# unijoysticle.net
KiCad netlist of a schematic drawn in EAGLE
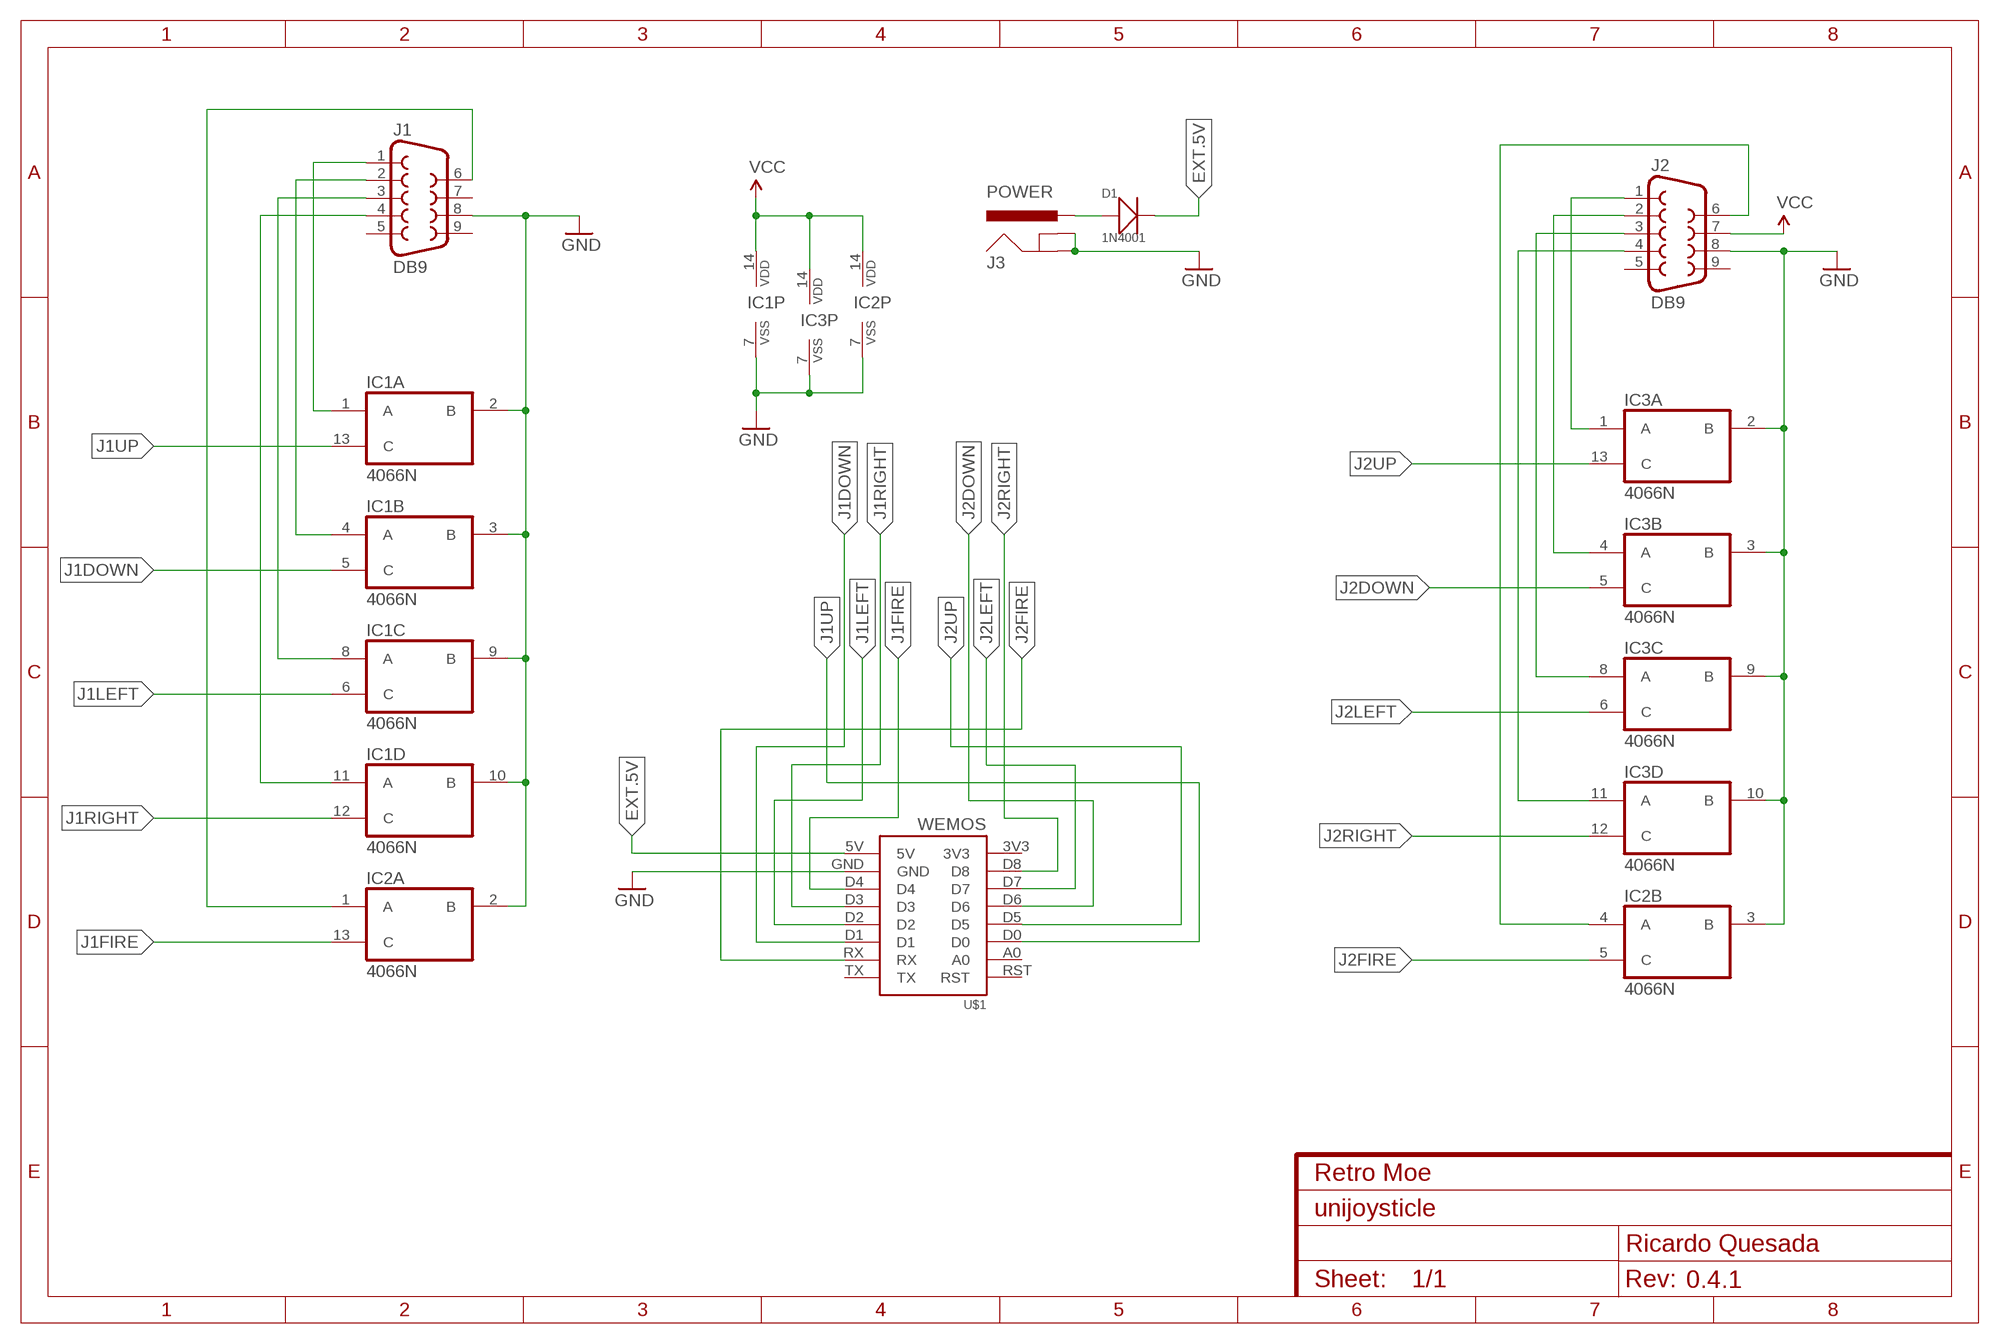
[diagram p0: schematic, sheet 1]

(export (version "E")
  (design (tool "Eeschema 10.0.6"))
  (components
    (comp (ref "D1")
      (value "1N4001")
      (footprint "eagle-import:DO-41")
      (libsource (lib "eagle-import") (part "DIP-DIODE-50V-1A-1N4001(DO-41)"))
    )
    (comp (ref "IC1")
      (value "4066N")
      (footprint "eagle-import:DIL14")
      (fields
        (field (name "MF") "TEXAS INSTRUMENTS")
        (field (name "MPN") "SN74HC4066N")
        (field (name "OC_NEWARK") "76C3574")
      )
      (libsource (lib "eagle-import") (part "4066N"))
    )
    (comp (ref "IC2")
      (value "4066N")
      (footprint "eagle-import:DIL14")
      (fields
        (field (name "MF") "TEXAS INSTRUMENTS")
        (field (name "MPN") "SN74HC4066N")
        (field (name "OC_NEWARK") "76C3574")
      )
      (libsource (lib "eagle-import") (part "4066N"))
    )
    (comp (ref "IC3")
      (value "4066N")
      (footprint "eagle-import:DIL14")
      (fields
        (field (name "MF") "TEXAS INSTRUMENTS")
        (field (name "MPN") "SN74HC4066N")
        (field (name "OC_NEWARK") "76C3574")
      )
      (libsource (lib "eagle-import") (part "4066N"))
    )
    (comp (ref "J1")
      (value "DB9")
      (footprint "eagle-import:DB9")
      (fields (field (name "MPN") "618009231121"))
      (libsource (lib "eagle-import") (part "DB9FEMALE"))
    )
    (comp (ref "J2")
      (value "DB9")
      (footprint "eagle-import:DB9")
      (fields (field (name "MPN") "618009231121"))
      (libsource (lib "eagle-import") (part "DB9FEMALE"))
    )
    (comp (ref "J3")
      (value "POWER")
      (footprint "eagle-import:POWER_JACK_SLOT")
      (libsource (lib "eagle-import") (part "POWER_JACKSLT"))
    )
    (comp (ref "U$1")
      (value "WEMOS")
      (footprint "eagle-import:WEMOS")
      (libsource (lib "eagle-import") (part "WEMOS"))
    )
  )
  (nets
    (net (code "1") (name "EXT.5V") (class "Default")
      (node (ref "D1") (pin "2") (pinfunction "-_2") (pintype "passive"))
      (node (ref "U$1") (pin "5V") (pinfunction "5V_5V") (pintype "bidirectional"))
    )
    (net (code "2") (name "GND") (class "Default")
      (node (ref "IC1") (pin "10") (pinfunction "B_10") (pintype "tri_state"))
      (node (ref "IC1") (pin "2") (pinfunction "B_2") (pintype "tri_state"))
      (node (ref "IC1") (pin "3") (pinfunction "B_3") (pintype "tri_state"))
      (node (ref "IC1") (pin "7") (pinfunction "VSS_7") (pintype "power_in"))
      (node (ref "IC1") (pin "9") (pinfunction "B_9") (pintype "tri_state"))
      (node (ref "IC2") (pin "2") (pinfunction "B_2") (pintype "tri_state"))
      (node (ref "IC2") (pin "3") (pinfunction "B_3") (pintype "tri_state"))
      (node (ref "IC2") (pin "7") (pinfunction "VSS_7") (pintype "power_in"))
      (node (ref "IC3") (pin "10") (pinfunction "B_10") (pintype "tri_state"))
      (node (ref "IC3") (pin "2") (pinfunction "B_2") (pintype "tri_state"))
      (node (ref "IC3") (pin "3") (pinfunction "B_3") (pintype "tri_state"))
      (node (ref "IC3") (pin "7") (pinfunction "VSS_7") (pintype "power_in"))
      (node (ref "IC3") (pin "9") (pinfunction "B_9") (pintype "tri_state"))
      (node (ref "J1") (pin "8") (pinfunction "8_8") (pintype "passive"))
      (node (ref "J2") (pin "8") (pinfunction "8_8") (pintype "passive"))
      (node (ref "J3") (pin "GND@1") (pinfunction "GNDBREAK_GND@1") (pintype "bidirectional"))
      (node (ref "J3") (pin "GND@2") (pinfunction "GND_GND@2") (pintype "bidirectional"))
      (node (ref "U$1") (pin "GND") (pinfunction "GND_GND") (pintype "bidirectional"))
    )
    (net (code "3") (name "J1DOWN") (class "Default")
      (node (ref "IC1") (pin "5") (pinfunction "C_5") (pintype "input"))
      (node (ref "U$1") (pin "D1") (pinfunction "D1_D1") (pintype "bidirectional"))
    )
    (net (code "4") (name "J1FIRE") (class "Default")
      (node (ref "IC2") (pin "13") (pinfunction "C_13") (pintype "input"))
      (node (ref "U$1") (pin "D4") (pinfunction "D4_D4") (pintype "bidirectional"))
    )
    (net (code "5") (name "J1LEFT") (class "Default")
      (node (ref "IC1") (pin "6") (pinfunction "C_6") (pintype "input"))
      (node (ref "U$1") (pin "D2") (pinfunction "D2_D2") (pintype "bidirectional"))
    )
    (net (code "6") (name "J1RIGHT") (class "Default")
      (node (ref "IC1") (pin "12") (pinfunction "C_12") (pintype "input"))
      (node (ref "U$1") (pin "D3") (pinfunction "D3_D3") (pintype "bidirectional"))
    )
    (net (code "7") (name "J1UP") (class "Default")
      (node (ref "IC1") (pin "13") (pinfunction "C_13") (pintype "input"))
      (node (ref "U$1") (pin "D0") (pinfunction "D0_D0") (pintype "bidirectional"))
    )
    (net (code "8") (name "J2DOWN") (class "Default")
      (node (ref "IC3") (pin "5") (pinfunction "C_5") (pintype "input"))
      (node (ref "U$1") (pin "D6") (pinfunction "D6_D6") (pintype "bidirectional"))
    )
    (net (code "9") (name "J2FIRE") (class "Default")
      (node (ref "IC2") (pin "5") (pinfunction "C_5") (pintype "input"))
      (node (ref "U$1") (pin "RX") (pinfunction "RX_RX") (pintype "bidirectional"))
    )
    (net (code "10") (name "J2LEFT") (class "Default")
      (node (ref "IC3") (pin "6") (pinfunction "C_6") (pintype "input"))
      (node (ref "U$1") (pin "D7") (pinfunction "D7_D7") (pintype "bidirectional"))
    )
    (net (code "11") (name "J2RIGHT") (class "Default")
      (node (ref "IC3") (pin "12") (pinfunction "C_12") (pintype "input"))
      (node (ref "U$1") (pin "D8") (pinfunction "D8_D8") (pintype "bidirectional"))
    )
    (net (code "12") (name "J2UP") (class "Default")
      (node (ref "IC3") (pin "13") (pinfunction "C_13") (pintype "input"))
      (node (ref "U$1") (pin "D5") (pinfunction "D5_D5") (pintype "bidirectional"))
    )
    (net (code "13") (name "Net-(D1-+)") (class "Default")
      (node (ref "D1") (pin "1") (pinfunction "+_1") (pintype "passive"))
      (node (ref "J3") (pin "PWR") (pinfunction "PWR_PWR") (pintype "bidirectional"))
    )
    (net (code "14") (name "Net-(IC1A-A)") (class "Default")
      (node (ref "IC1") (pin "1") (pinfunction "A_1") (pintype "tri_state"))
      (node (ref "J1") (pin "1") (pinfunction "1_1") (pintype "passive"))
    )
    (net (code "15") (name "Net-(IC1B-A)") (class "Default")
      (node (ref "IC1") (pin "4") (pinfunction "A_4") (pintype "tri_state"))
      (node (ref "J1") (pin "2") (pinfunction "2_2") (pintype "passive"))
    )
    (net (code "16") (name "Net-(IC1C-A)") (class "Default")
      (node (ref "IC1") (pin "8") (pinfunction "A_8") (pintype "tri_state"))
      (node (ref "J1") (pin "3") (pinfunction "3_3") (pintype "passive"))
    )
    (net (code "17") (name "Net-(IC1D-A)") (class "Default")
      (node (ref "IC1") (pin "11") (pinfunction "A_11") (pintype "tri_state"))
      (node (ref "J1") (pin "4") (pinfunction "4_4") (pintype "passive"))
    )
    (net (code "18") (name "Net-(IC2A-A)") (class "Default")
      (node (ref "IC2") (pin "1") (pinfunction "A_1") (pintype "tri_state"))
      (node (ref "J1") (pin "6") (pinfunction "6_6") (pintype "passive"))
    )
    (net (code "19") (name "Net-(IC2B-A)") (class "Default")
      (node (ref "IC2") (pin "4") (pinfunction "A_4") (pintype "tri_state"))
      (node (ref "J2") (pin "6") (pinfunction "6_6") (pintype "passive"))
    )
    (net (code "20") (name "Net-(IC3A-A)") (class "Default")
      (node (ref "IC3") (pin "1") (pinfunction "A_1") (pintype "tri_state"))
      (node (ref "J2") (pin "1") (pinfunction "1_1") (pintype "passive"))
    )
    (net (code "21") (name "Net-(IC3B-A)") (class "Default")
      (node (ref "IC3") (pin "4") (pinfunction "A_4") (pintype "tri_state"))
      (node (ref "J2") (pin "2") (pinfunction "2_2") (pintype "passive"))
    )
    (net (code "22") (name "Net-(IC3C-A)") (class "Default")
      (node (ref "IC3") (pin "8") (pinfunction "A_8") (pintype "tri_state"))
      (node (ref "J2") (pin "3") (pinfunction "3_3") (pintype "passive"))
    )
    (net (code "23") (name "Net-(IC3D-A)") (class "Default")
      (node (ref "IC3") (pin "11") (pinfunction "A_11") (pintype "tri_state"))
      (node (ref "J2") (pin "4") (pinfunction "4_4") (pintype "passive"))
    )
    (net (code "24") (name "VCC") (class "Default")
      (node (ref "IC1") (pin "14") (pinfunction "VDD_14") (pintype "power_in"))
      (node (ref "IC2") (pin "14") (pinfunction "VDD_14") (pintype "power_in"))
      (node (ref "IC3") (pin "14") (pinfunction "VDD_14") (pintype "power_in"))
      (node (ref "J2") (pin "7") (pinfunction "7_7") (pintype "passive"))
    )
    (net (code "25") (name "unconnected-(J1-Pad5)") (class "Default")
      (node (ref "J1") (pin "5") (pinfunction "5_5") (pintype "passive"))
    )
    (net (code "26") (name "unconnected-(J1-Pad7)") (class "Default")
      (node (ref "J1") (pin "7") (pinfunction "7_7") (pintype "passive"))
    )
    (net (code "27") (name "unconnected-(J1-Pad9)") (class "Default")
      (node (ref "J1") (pin "9") (pinfunction "9_9") (pintype "passive"))
    )
    (net (code "28") (name "unconnected-(J2-Pad5)") (class "Default")
      (node (ref "J2") (pin "5") (pinfunction "5_5") (pintype "passive"))
    )
    (net (code "29") (name "unconnected-(J2-Pad9)") (class "Default")
      (node (ref "J2") (pin "9") (pinfunction "9_9") (pintype "passive"))
    )
    (net (code "30") (name "unconnected-(U$1-Pad3V3)") (class "Default")
      (node (ref "U$1") (pin "3V3") (pinfunction "3V3_3V3") (pintype "bidirectional"))
    )
    (net (code "31") (name "unconnected-(U$1-PadA0)") (class "Default")
      (node (ref "U$1") (pin "A0") (pinfunction "A0_A0") (pintype "bidirectional"))
    )
    (net (code "32") (name "unconnected-(U$1-PadRST)") (class "Default")
      (node (ref "U$1") (pin "RST") (pinfunction "RST_RST") (pintype "bidirectional"))
    )
    (net (code "33") (name "unconnected-(U$1-PadTX)") (class "Default")
      (node (ref "U$1") (pin "TX") (pinfunction "TX_TX") (pintype "bidirectional"))
    )
  )
)
